# 16Ch_Milti_INA219.net
KiCad netlist of a schematic drawn in Altium Designer
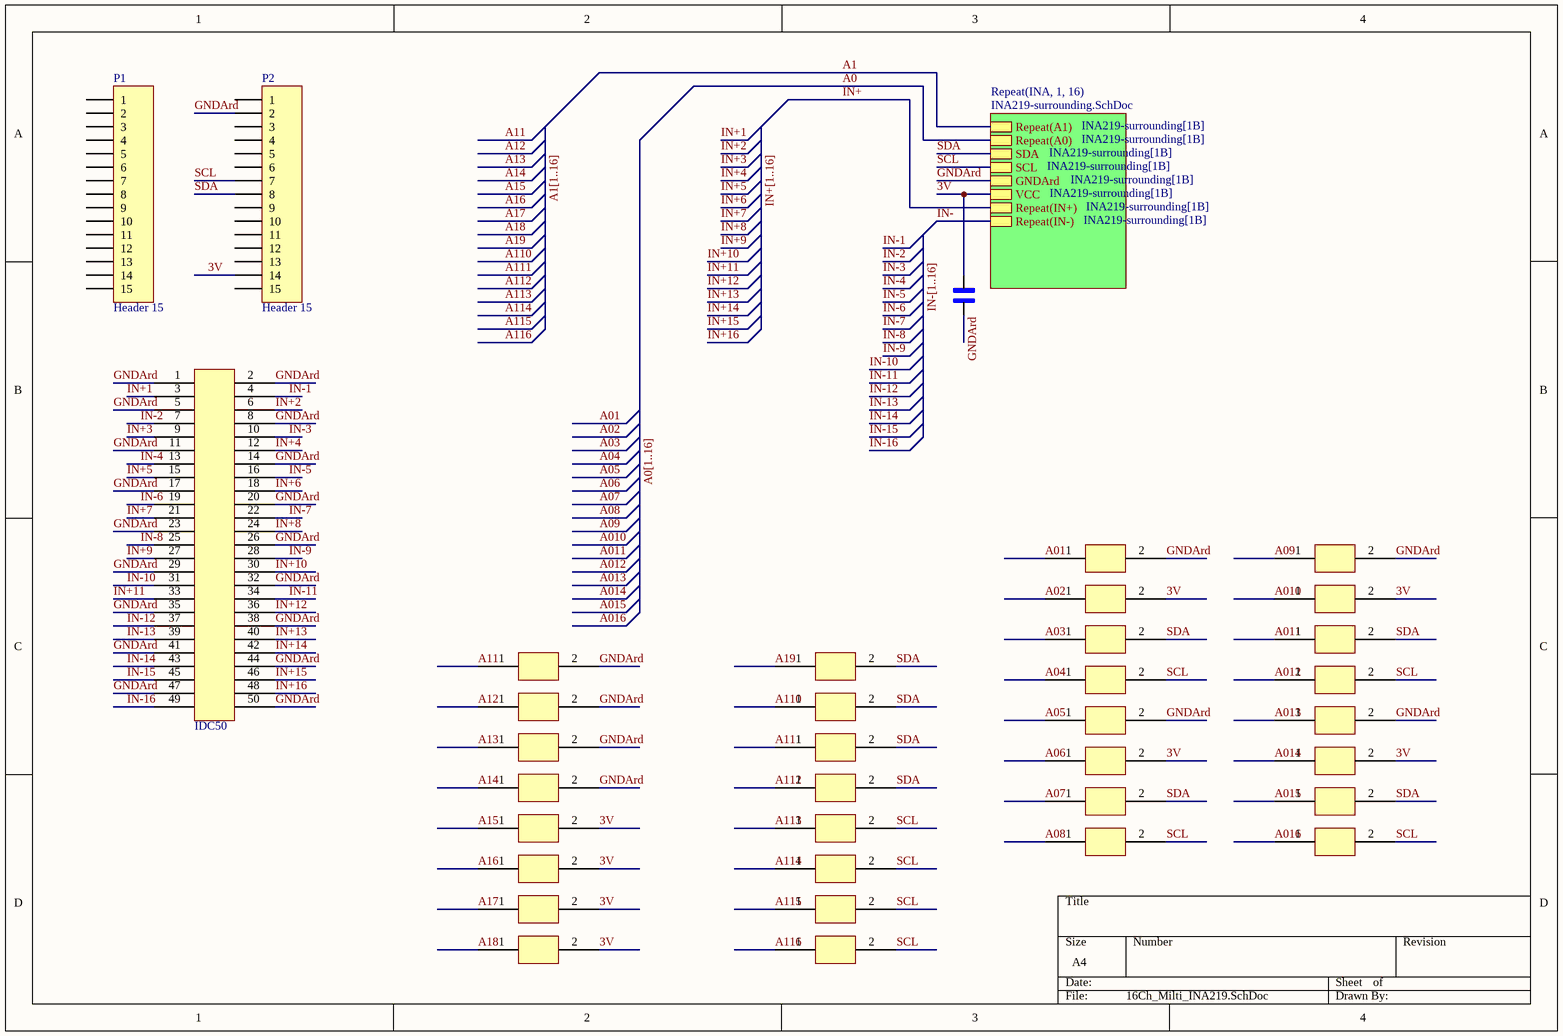
[diagram p0: 16Ch_Milti_INA219.SchDoc]

(export (version "E")
  (design (tool "Eeschema 10.0.6"))
  (components
    (comp (ref "*1") (value "IDC50") (footprint "IDC50") (libsource (lib "eic_lib") (part "IDC50")))
    (comp (ref "P1")
      (value "Header 15")
      (footprint "HDR1X15")
      (description "Header, 15-Pin")
      (fields (field (name "PUBLISHER") "Altium Limited"))
      (libsource (lib "Miscellaneous Connectors") (part "Header 15"))
    )
    (comp (ref "P2")
      (value "Header 15")
      (footprint "HDR1X15")
      (description "Header, 15-Pin")
      (fields (field (name "PUBLISHER") "Altium Limited"))
      (libsource (lib "Miscellaneous Connectors") (part "Header 15"))
    )
    (comp (ref "R1") (value "RES0603") (footprint "RES0603") (libsource (lib "eic_lib") (part "RES0603")))
    (comp (ref "R2") (value "RES0603") (footprint "RES0603") (libsource (lib "eic_lib") (part "RES0603")))
    (comp (ref "R3") (value "RES0603") (footprint "RES0603") (libsource (lib "eic_lib") (part "RES0603")))
    (comp (ref "R4") (value "RES0603") (footprint "RES0603") (libsource (lib "eic_lib") (part "RES0603")))
    (comp (ref "R5") (value "RES0603") (footprint "RES0603") (libsource (lib "eic_lib") (part "RES0603")))
    (comp (ref "R6") (value "RES0603") (footprint "RES0603") (libsource (lib "eic_lib") (part "RES0603")))
    (comp (ref "R7") (value "RES0603") (footprint "RES0603") (libsource (lib "eic_lib") (part "RES0603")))
    (comp (ref "R8") (value "RES0603") (footprint "RES0603") (libsource (lib "eic_lib") (part "RES0603")))
    (comp (ref "R9") (value "RES0603") (footprint "RES0603") (libsource (lib "eic_lib") (part "RES0603")))
    (comp (ref "R10") (value "RES0603") (footprint "RES0603") (libsource (lib "eic_lib") (part "RES0603")))
    (comp (ref "R11") (value "RES0603") (footprint "RES0603") (libsource (lib "eic_lib") (part "RES0603")))
    (comp (ref "R12") (value "RES0603") (footprint "RES0603") (libsource (lib "eic_lib") (part "RES0603")))
    (comp (ref "R13") (value "RES0603") (footprint "RES0603") (libsource (lib "eic_lib") (part "RES0603")))
    (comp (ref "R14") (value "RES0603") (footprint "RES0603") (libsource (lib "eic_lib") (part "RES0603")))
    (comp (ref "R15") (value "RES0603") (footprint "RES0603") (libsource (lib "eic_lib") (part "RES0603")))
    (comp (ref "R16") (value "RES0603") (footprint "RES0603") (libsource (lib "eic_lib") (part "RES0603")))
    (comp (ref "R17") (value "RES0603") (footprint "RES0603") (libsource (lib "eic_lib") (part "RES0603")))
    (comp (ref "R18") (value "RES0603") (footprint "RES0603") (libsource (lib "eic_lib") (part "RES0603")))
    (comp (ref "R19") (value "RES0603") (footprint "RES0603") (libsource (lib "eic_lib") (part "RES0603")))
    (comp (ref "R20") (value "RES0603") (footprint "RES0603") (libsource (lib "eic_lib") (part "RES0603")))
    (comp (ref "R21") (value "RES0603") (footprint "RES0603") (libsource (lib "eic_lib") (part "RES0603")))
    (comp (ref "R22") (value "RES0603") (footprint "RES0603") (libsource (lib "eic_lib") (part "RES0603")))
    (comp (ref "R23") (value "RES0603") (footprint "RES0603") (libsource (lib "eic_lib") (part "RES0603")))
    (comp (ref "R24") (value "RES0603") (footprint "RES0603") (libsource (lib "eic_lib") (part "RES0603")))
    (comp (ref "R25") (value "RES0603") (footprint "RES0603") (libsource (lib "eic_lib") (part "RES0603")))
    (comp (ref "R26") (value "RES0603") (footprint "RES0603") (libsource (lib "eic_lib") (part "RES0603")))
    (comp (ref "R27") (value "RES0603") (footprint "RES0603") (libsource (lib "eic_lib") (part "RES0603")))
    (comp (ref "R28") (value "RES0603") (footprint "RES0603") (libsource (lib "eic_lib") (part "RES0603")))
    (comp (ref "R29") (value "RES0603") (footprint "RES0603") (libsource (lib "eic_lib") (part "RES0603")))
    (comp (ref "R30") (value "RES0603") (footprint "RES0603") (libsource (lib "eic_lib") (part "RES0603")))
    (comp (ref "R31") (value "RES0603") (footprint "RES0603") (libsource (lib "eic_lib") (part "RES0603")))
    (comp (ref "R32") (value "RES0603") (footprint "RES0603") (libsource (lib "eic_lib") (part "RES0603")))
    (comp (ref "С1") (value "CAP0805") (footprint "CAP0805") (libsource (lib "eic_lib") (part "CAP0805")))
  )
  (nets
    (net (code "1") (name "/3V") (class "Default")
      (node (ref "P2") (pin "14") (pinfunction "14_14") (pintype "passive"))
      (node (ref "R18") (pin "2") (pintype "passive"))
      (node (ref "R22") (pin "2") (pintype "passive"))
      (node (ref "R26") (pin "2") (pintype "passive"))
      (node (ref "R30") (pin "2") (pintype "passive"))
      (node (ref "R5") (pin "2") (pintype "passive"))
      (node (ref "R6") (pin "2") (pintype "passive"))
      (node (ref "R7") (pin "2") (pintype "passive"))
      (node (ref "R8") (pin "2") (pintype "passive"))
      (node (ref "С1") (pin "2") (pinfunction "2_2") (pintype "passive"))
    )
    (net (code "5") (name "/A01") (class "Default") (node (ref "R17") (pin "1") (pintype "passive")))
    (net (code "7") (name "/A02") (class "Default") (node (ref "R18") (pin "1") (pintype "passive")))
    (net (code "8") (name "/A03") (class "Default") (node (ref "R19") (pin "1") (pintype "passive")))
    (net (code "9") (name "/A04") (class "Default") (node (ref "R20") (pin "1") (pintype "passive")))
    (net (code "10") (name "/A05") (class "Default") (node (ref "R21") (pin "1") (pintype "passive")))
    (net (code "11") (name "/A06") (class "Default") (node (ref "R22") (pin "1") (pintype "passive")))
    (net (code "12") (name "/A07") (class "Default") (node (ref "R23") (pin "1") (pintype "passive")))
    (net (code "13") (name "/A08") (class "Default") (node (ref "R24") (pin "1") (pintype "passive")))
    (net (code "14") (name "/A09") (class "Default") (node (ref "R25") (pin "1") (pintype "passive")))
    (net (code "15") (name "/A010") (class "Default") (node (ref "R26") (pin "1") (pintype "passive")))
    (net (code "16") (name "/A011") (class "Default") (node (ref "R27") (pin "1") (pintype "passive")))
    (net (code "17") (name "/A11") (class "Default") (node (ref "R1") (pin "1") (pintype "passive")))
    (net (code "18") (name "/A12") (class "Default") (node (ref "R2") (pin "1") (pintype "passive")))
    (net (code "19") (name "/A012") (class "Default") (node (ref "R28") (pin "1") (pintype "passive")))
    (net (code "20") (name "/A013") (class "Default") (node (ref "R29") (pin "1") (pintype "passive")))
    (net (code "21") (name "/A13") (class "Default") (node (ref "R3") (pin "1") (pintype "passive")))
    (net (code "22") (name "/A14") (class "Default") (node (ref "R4") (pin "1") (pintype "passive")))
    (net (code "23") (name "/A014") (class "Default") (node (ref "R30") (pin "1") (pintype "passive")))
    (net (code "24") (name "/A015") (class "Default") (node (ref "R31") (pin "1") (pintype "passive")))
    (net (code "25") (name "/A15") (class "Default") (node (ref "R5") (pin "1") (pintype "passive")))
    (net (code "26") (name "/A16") (class "Default") (node (ref "R6") (pin "1") (pintype "passive")))
    (net (code "27") (name "/A016") (class "Default") (node (ref "R32") (pin "1") (pintype "passive")))
    (net (code "28") (name "/A17") (class "Default") (node (ref "R7") (pin "1") (pintype "passive")))
    (net (code "29") (name "/A18") (class "Default") (node (ref "R8") (pin "1") (pintype "passive")))
    (net (code "30") (name "/A19") (class "Default") (node (ref "R9") (pin "1") (pintype "passive")))
    (net (code "31") (name "/A110") (class "Default") (node (ref "R10") (pin "1") (pintype "passive")))
    (net (code "32") (name "/A111") (class "Default") (node (ref "R11") (pin "1") (pintype "passive")))
    (net (code "33") (name "/A112") (class "Default") (node (ref "R12") (pin "1") (pintype "passive")))
    (net (code "34") (name "/A113") (class "Default") (node (ref "R13") (pin "1") (pintype "passive")))
    (net (code "35") (name "/A114") (class "Default") (node (ref "R14") (pin "1") (pintype "passive")))
    (net (code "36") (name "/A115") (class "Default") (node (ref "R15") (pin "1") (pintype "passive")))
    (net (code "37") (name "/A116") (class "Default") (node (ref "R16") (pin "1") (pintype "passive")))
    (net (code "38") (name "/GNDArd") (class "Default")
      (node (ref "*1") (pin "1") (pintype "passive"))
      (node (ref "*1") (pin "11") (pintype "passive"))
      (node (ref "*1") (pin "14") (pintype "passive"))
      (node (ref "*1") (pin "17") (pintype "passive"))
      (node (ref "*1") (pin "2") (pintype "passive"))
      (node (ref "*1") (pin "20") (pintype "passive"))
      (node (ref "*1") (pin "23") (pintype "passive"))
      (node (ref "*1") (pin "26") (pintype "passive"))
      (node (ref "*1") (pin "29") (pintype "passive"))
      (node (ref "*1") (pin "32") (pintype "passive"))
      (node (ref "*1") (pin "35") (pintype "passive"))
      (node (ref "*1") (pin "38") (pintype "passive"))
      (node (ref "*1") (pin "41") (pintype "passive"))
      (node (ref "*1") (pin "44") (pintype "passive"))
      (node (ref "*1") (pin "47") (pintype "passive"))
      (node (ref "*1") (pin "5") (pintype "passive"))
      (node (ref "*1") (pin "50") (pintype "passive"))
      (node (ref "*1") (pin "8") (pintype "passive"))
      (node (ref "P2") (pin "2") (pinfunction "2_2") (pintype "passive"))
      (node (ref "R1") (pin "2") (pintype "passive"))
      (node (ref "R17") (pin "2") (pintype "passive"))
      (node (ref "R2") (pin "2") (pintype "passive"))
      (node (ref "R21") (pin "2") (pintype "passive"))
      (node (ref "R25") (pin "2") (pintype "passive"))
      (node (ref "R29") (pin "2") (pintype "passive"))
      (node (ref "R3") (pin "2") (pintype "passive"))
      (node (ref "R4") (pin "2") (pintype "passive"))
      (node (ref "С1") (pin "1") (pinfunction "1_1") (pintype "passive"))
    )
    (net (code "40") (name "/IN+1") (class "Default") (node (ref "*1") (pin "3") (pintype "passive")))
    (net (code "41") (name "/IN+2") (class "Default") (node (ref "*1") (pin "6") (pintype "passive")))
    (net (code "42") (name "/IN+3") (class "Default") (node (ref "*1") (pin "9") (pintype "passive")))
    (net (code "43") (name "/IN+4") (class "Default") (node (ref "*1") (pin "12") (pintype "passive")))
    (net (code "44") (name "/IN+5") (class "Default") (node (ref "*1") (pin "15") (pintype "passive")))
    (net (code "45") (name "/IN+6") (class "Default") (node (ref "*1") (pin "18") (pintype "passive")))
    (net (code "46") (name "/IN+7") (class "Default") (node (ref "*1") (pin "21") (pintype "passive")))
    (net (code "47") (name "/IN+8") (class "Default") (node (ref "*1") (pin "24") (pintype "passive")))
    (net (code "48") (name "/IN+9") (class "Default") (node (ref "*1") (pin "27") (pintype "passive")))
    (net (code "49") (name "/IN+10") (class "Default") (node (ref "*1") (pin "30") (pintype "passive")))
    (net (code "50") (name "/IN+11") (class "Default") (node (ref "*1") (pin "33") (pintype "passive")))
    (net (code "51") (name "/IN+12") (class "Default") (node (ref "*1") (pin "36") (pintype "passive")))
    (net (code "52") (name "/IN+13") (class "Default") (node (ref "*1") (pin "40") (pintype "passive")))
    (net (code "53") (name "/IN+14") (class "Default") (node (ref "*1") (pin "42") (pintype "passive")))
    (net (code "54") (name "/IN+15") (class "Default") (node (ref "*1") (pin "46") (pintype "passive")))
    (net (code "55") (name "/IN+16") (class "Default") (node (ref "*1") (pin "48") (pintype "passive")))
    (net (code "58") (name "/IN-1") (class "Default") (node (ref "*1") (pin "4") (pintype "passive")))
    (net (code "59") (name "/IN-2") (class "Default") (node (ref "*1") (pin "7") (pintype "passive")))
    (net (code "60") (name "/IN-3") (class "Default") (node (ref "*1") (pin "10") (pintype "passive")))
    (net (code "61") (name "/IN-4") (class "Default") (node (ref "*1") (pin "13") (pintype "passive")))
    (net (code "62") (name "/IN-5") (class "Default") (node (ref "*1") (pin "16") (pintype "passive")))
    (net (code "63") (name "/IN-6") (class "Default") (node (ref "*1") (pin "19") (pintype "passive")))
    (net (code "64") (name "/IN-7") (class "Default") (node (ref "*1") (pin "22") (pintype "passive")))
    (net (code "65") (name "/IN-8") (class "Default") (node (ref "*1") (pin "25") (pintype "passive")))
    (net (code "66") (name "/IN-9") (class "Default") (node (ref "*1") (pin "28") (pintype "passive")))
    (net (code "67") (name "/IN-10") (class "Default") (node (ref "*1") (pin "31") (pintype "passive")))
    (net (code "68") (name "/IN-11") (class "Default") (node (ref "*1") (pin "34") (pintype "passive")))
    (net (code "69") (name "/IN-12") (class "Default") (node (ref "*1") (pin "37") (pintype "passive")))
    (net (code "70") (name "/IN-13") (class "Default") (node (ref "*1") (pin "39") (pintype "passive")))
    (net (code "71") (name "/IN-14") (class "Default") (node (ref "*1") (pin "43") (pintype "passive")))
    (net (code "72") (name "/IN-15") (class "Default") (node (ref "*1") (pin "45") (pintype "passive")))
    (net (code "73") (name "/IN-16") (class "Default") (node (ref "*1") (pin "49") (pintype "passive")))
    (net (code "75") (name "/SCL") (class "Default")
      (node (ref "P2") (pin "7") (pinfunction "7_7") (pintype "passive"))
      (node (ref "R13") (pin "2") (pintype "passive"))
      (node (ref "R14") (pin "2") (pintype "passive"))
      (node (ref "R15") (pin "2") (pintype "passive"))
      (node (ref "R16") (pin "2") (pintype "passive"))
      (node (ref "R20") (pin "2") (pintype "passive"))
      (node (ref "R24") (pin "2") (pintype "passive"))
      (node (ref "R28") (pin "2") (pintype "passive"))
      (node (ref "R32") (pin "2") (pintype "passive"))
    )
    (net (code "76") (name "/SDA") (class "Default")
      (node (ref "P2") (pin "8") (pinfunction "8_8") (pintype "passive"))
      (node (ref "R10") (pin "2") (pintype "passive"))
      (node (ref "R11") (pin "2") (pintype "passive"))
      (node (ref "R12") (pin "2") (pintype "passive"))
      (node (ref "R19") (pin "2") (pintype "passive"))
      (node (ref "R23") (pin "2") (pintype "passive"))
      (node (ref "R27") (pin "2") (pintype "passive"))
      (node (ref "R31") (pin "2") (pintype "passive"))
      (node (ref "R9") (pin "2") (pintype "passive"))
    )
    (net (code "77") (name "unconnected-(P1-Pad1)") (class "Default")
      (node (ref "P1") (pin "1") (pinfunction "1_1") (pintype "passive"))
    )
    (net (code "78") (name "unconnected-(P1-Pad2)") (class "Default")
      (node (ref "P1") (pin "2") (pinfunction "2_2") (pintype "passive"))
    )
    (net (code "79") (name "unconnected-(P1-Pad3)") (class "Default")
      (node (ref "P1") (pin "3") (pinfunction "3_3") (pintype "passive"))
    )
    (net (code "80") (name "unconnected-(P1-Pad4)") (class "Default")
      (node (ref "P1") (pin "4") (pinfunction "4_4") (pintype "passive"))
    )
    (net (code "81") (name "unconnected-(P1-Pad5)") (class "Default")
      (node (ref "P1") (pin "5") (pinfunction "5_5") (pintype "passive"))
    )
    (net (code "82") (name "unconnected-(P1-Pad6)") (class "Default")
      (node (ref "P1") (pin "6") (pinfunction "6_6") (pintype "passive"))
    )
    (net (code "83") (name "unconnected-(P1-Pad7)") (class "Default")
      (node (ref "P1") (pin "7") (pinfunction "7_7") (pintype "passive"))
    )
    (net (code "84") (name "unconnected-(P1-Pad8)") (class "Default")
      (node (ref "P1") (pin "8") (pinfunction "8_8") (pintype "passive"))
    )
    (net (code "85") (name "unconnected-(P1-Pad9)") (class "Default")
      (node (ref "P1") (pin "9") (pinfunction "9_9") (pintype "passive"))
    )
    (net (code "86") (name "unconnected-(P1-Pad10)") (class "Default")
      (node (ref "P1") (pin "10") (pinfunction "10_10") (pintype "passive"))
    )
    (net (code "87") (name "unconnected-(P1-Pad11)") (class "Default")
      (node (ref "P1") (pin "11") (pinfunction "11_11") (pintype "passive"))
    )
    (net (code "88") (name "unconnected-(P1-Pad12)") (class "Default")
      (node (ref "P1") (pin "12") (pinfunction "12_12") (pintype "passive"))
    )
    (net (code "89") (name "unconnected-(P1-Pad13)") (class "Default")
      (node (ref "P1") (pin "13") (pinfunction "13_13") (pintype "passive"))
    )
    (net (code "90") (name "unconnected-(P1-Pad14)") (class "Default")
      (node (ref "P1") (pin "14") (pinfunction "14_14") (pintype "passive"))
    )
    (net (code "91") (name "unconnected-(P1-Pad15)") (class "Default")
      (node (ref "P1") (pin "15") (pinfunction "15_15") (pintype "passive"))
    )
    (net (code "92") (name "unconnected-(P2-Pad1)") (class "Default")
      (node (ref "P2") (pin "1") (pinfunction "1_1") (pintype "passive"))
    )
    (net (code "93") (name "unconnected-(P2-Pad3)") (class "Default")
      (node (ref "P2") (pin "3") (pinfunction "3_3") (pintype "passive"))
    )
    (net (code "94") (name "unconnected-(P2-Pad4)") (class "Default")
      (node (ref "P2") (pin "4") (pinfunction "4_4") (pintype "passive"))
    )
    (net (code "95") (name "unconnected-(P2-Pad5)") (class "Default")
      (node (ref "P2") (pin "5") (pinfunction "5_5") (pintype "passive"))
    )
    (net (code "96") (name "unconnected-(P2-Pad6)") (class "Default")
      (node (ref "P2") (pin "6") (pinfunction "6_6") (pintype "passive"))
    )
    (net (code "97") (name "unconnected-(P2-Pad9)") (class "Default")
      (node (ref "P2") (pin "9") (pinfunction "9_9") (pintype "passive"))
    )
    (net (code "98") (name "unconnected-(P2-Pad10)") (class "Default")
      (node (ref "P2") (pin "10") (pinfunction "10_10") (pintype "passive"))
    )
    (net (code "99") (name "unconnected-(P2-Pad11)") (class "Default")
      (node (ref "P2") (pin "11") (pinfunction "11_11") (pintype "passive"))
    )
    (net (code "100") (name "unconnected-(P2-Pad12)") (class "Default")
      (node (ref "P2") (pin "12") (pinfunction "12_12") (pintype "passive"))
    )
    (net (code "101") (name "unconnected-(P2-Pad13)") (class "Default")
      (node (ref "P2") (pin "13") (pinfunction "13_13") (pintype "passive"))
    )
    (net (code "102") (name "unconnected-(P2-Pad15)") (class "Default")
      (node (ref "P2") (pin "15") (pinfunction "15_15") (pintype "passive"))
    )
  )
)
